# Sheet2.net
KiCad netlist of a schematic drawn in Altium Designer
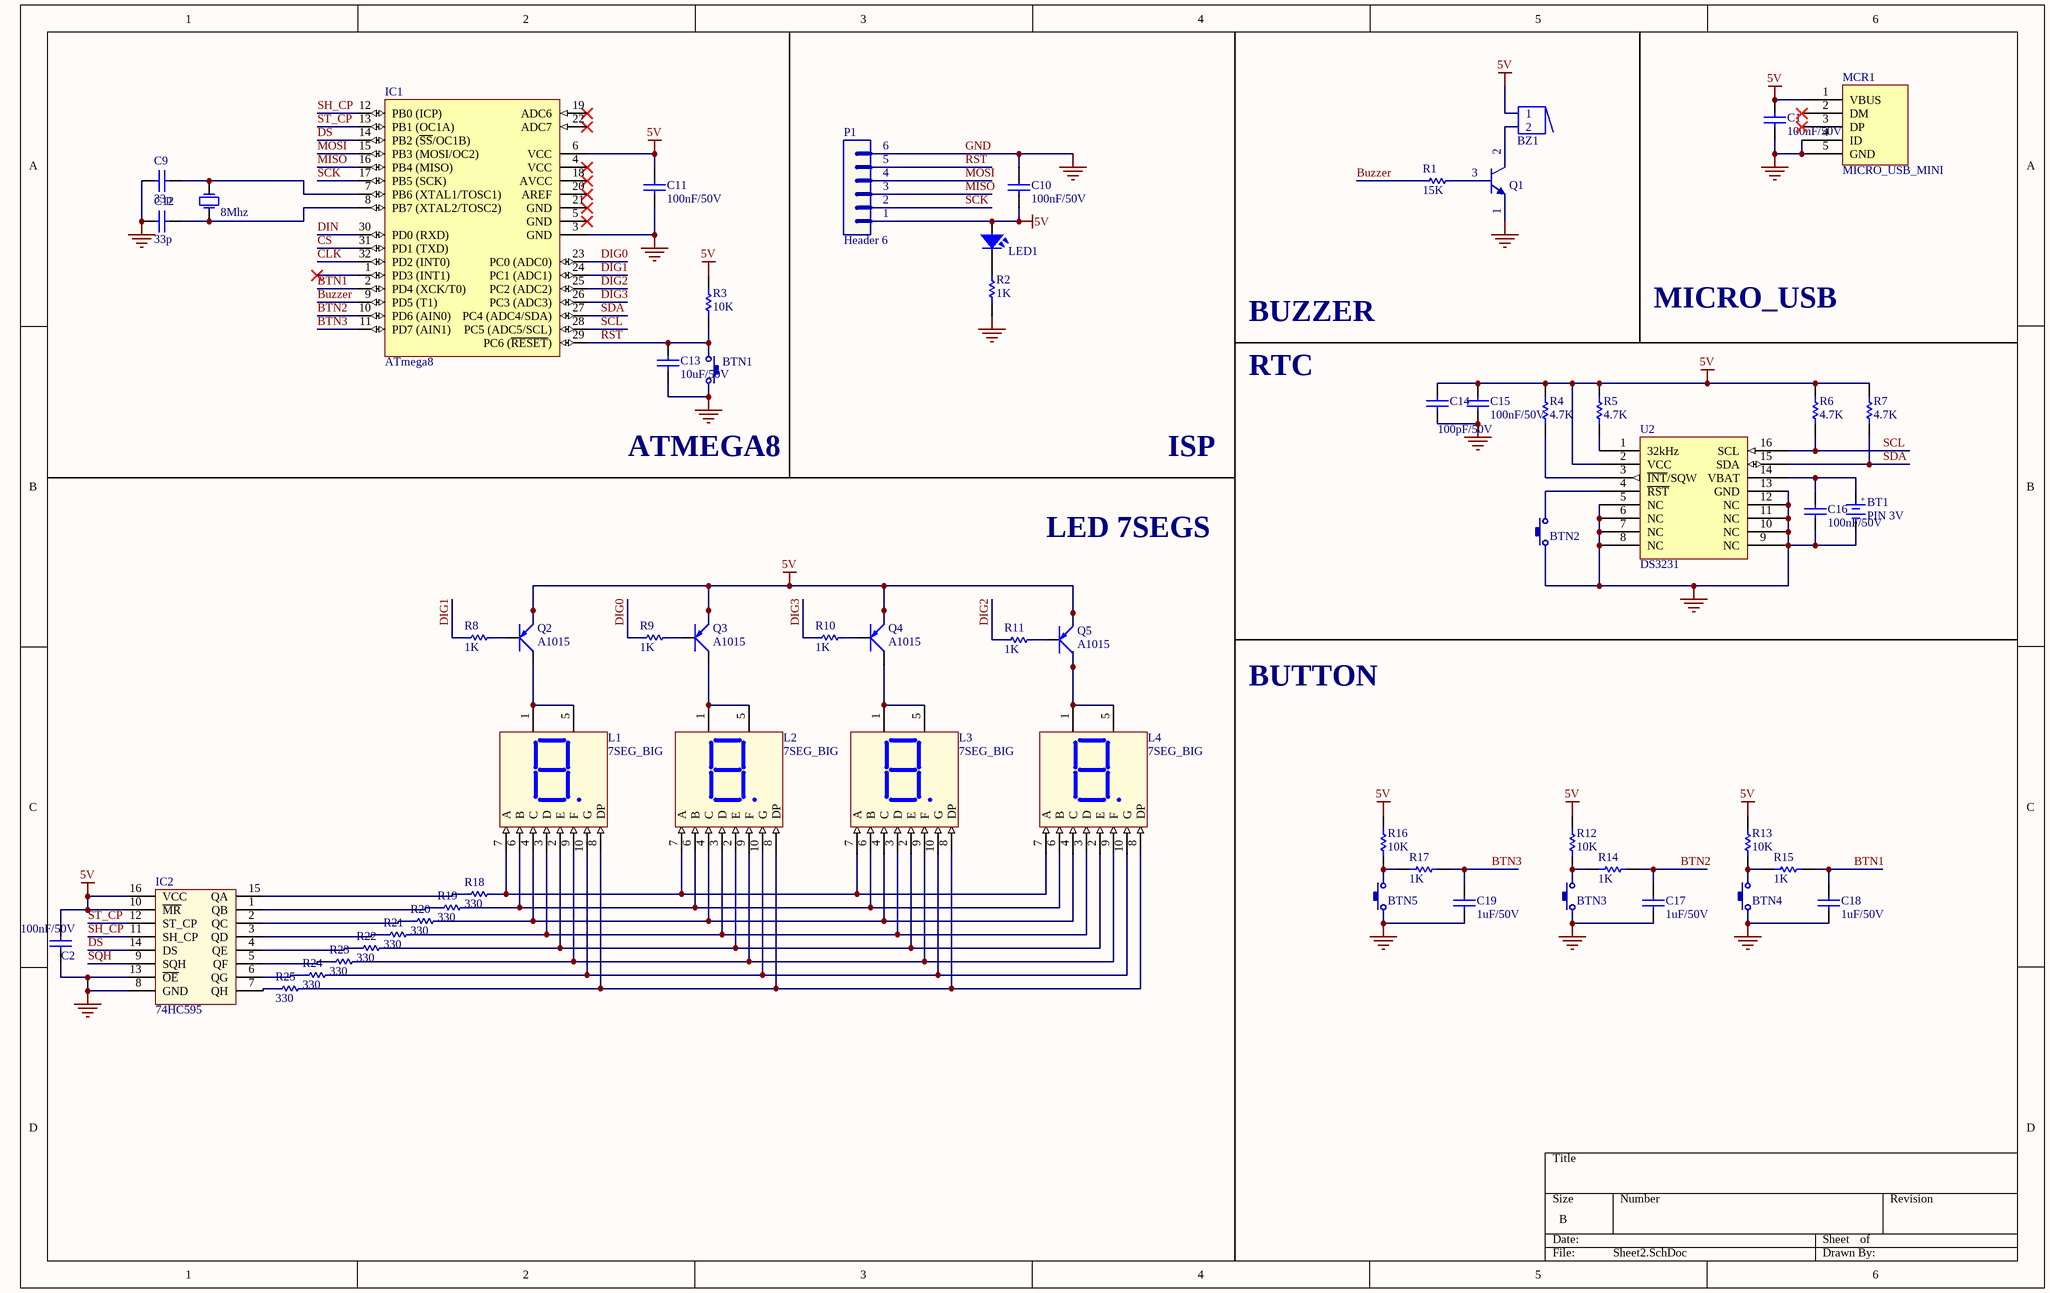
[diagram p0: Sheet2.SchDoc]

(export (version "E")
  (design (tool "Eeschema 10.0.6"))
  (components
    (comp (ref "BT1")
      (value "PIN 3V")
      (footprint "PIN3V")
      (description "Battery 3VDC")
      (libsource (lib "syhaunguyen") (part "PIN 3V"))
    )
    (comp (ref "BTN1") (value "Button") (footprint "Button") (libsource (lib "") (part "Button_1")))
    (comp (ref "BTN2")
      (value "Button")
      (footprint "Button")
      (libsource (lib "PIF_C16_2_lib") (part "Button"))
    )
    (comp (ref "BTN3")
      (value "Button")
      (footprint "Button")
      (libsource (lib "PIF_C16_2_lib") (part "Button"))
    )
    (comp (ref "BTN4")
      (value "Button")
      (footprint "Button")
      (libsource (lib "PIF_C16_2_lib") (part "Button"))
    )
    (comp (ref "BTN5")
      (value "Button")
      (footprint "Button")
      (libsource (lib "PIF_C16_2_lib") (part "Button"))
    )
    (comp (ref "BZ1") (value "Buzzer") (footprint "BUZZER") (libsource (lib "PIF_C16_2_lib") (part "Buzzer")))
    (comp (ref "C1")
      (value "100nF/50V")
      (footprint "CAP-SM-0805")
      (description "CAP CER 0.1UF 50V Y5V 0805")
      (fields
        (field (name "MANUFACTURER") "Samsung Electro-Mechanics")
        (field (name "MANUFACTURER PART NUMBER") "CL21F104ZBCNNNC")
      )
      (libsource (lib "Capacitor") (part "Cap-100nF-50V-0805"))
    )
    (comp (ref "C2")
      (value "100nF/50V")
      (footprint "CAP-SM-0805")
      (description "CAP CER 0.1UF 50V Y5V 0805")
      (fields
        (field (name "MANUFACTURER") "Samsung Electro-Mechanics")
        (field (name "MANUFACTURER PART NUMBER") "CL21F104ZBCNNNC")
      )
      (libsource (lib "Capacitor") (part "Cap-100nF-50V-0805"))
    )
    (comp (ref "C9")
      (value "33p")
      (footprint "Tu-pico")
      (description "Capacitor")
      (fields (field (name "Comment") "Capacitor Ceramic") (field (name "PUBLISHER") "Altium Limited"))
      (libsource (lib "My Library") (part "CapCeramic"))
    )
    (comp (ref "C10")
      (value "100nF/50V")
      (footprint "CAP-SM-0805")
      (description "CAP CER 0.1UF 50V Y5V 0805")
      (fields
        (field (name "MANUFACTURER") "Samsung Electro-Mechanics")
        (field (name "MANUFACTURER PART NUMBER") "CL21F104ZBCNNNC")
      )
      (libsource (lib "Capacitor") (part "Cap-100nF-50V-0805"))
    )
    (comp (ref "C11")
      (value "100nF/50V")
      (footprint "CAP-SM-0805")
      (description "CAP CER 0.1UF 50V Y5V 0805")
      (fields
        (field (name "MANUFACTURER") "Samsung Electro-Mechanics")
        (field (name "MANUFACTURER PART NUMBER") "CL21F104ZBCNNNC")
      )
      (libsource (lib "Capacitor") (part "Cap-100nF-50V-0805"))
    )
    (comp (ref "C12")
      (value "33p")
      (footprint "Tu-pico")
      (description "Capacitor")
      (fields (field (name "Comment") "Capacitor Ceramic") (field (name "PUBLISHER") "Altium Limited"))
      (libsource (lib "My Library") (part "CapCeramic"))
    )
    (comp (ref "C13")
      (value "10uF/50V")
      (footprint "CAP-SM-0805")
      (description "CAP CER 10UF 50V X5R 0805")
      (fields
        (field (name "MANUFACTURER") "Yageo")
        (field (name "MANUFACTURER PART NUMBER") "CC0805KKX5R9BB106")
      )
      (libsource (lib "Capacitor") (part "Cap-10uF-50V-0805"))
    )
    (comp (ref "C14")
      (value "100pF/50V")
      (footprint "CAP-SM-0805")
      (description "CAP CER 100PF 50V C0G/NP0 0805")
      (fields
        (field (name "MANUFACTURER") "KEMET")
        (field (name "MANUFACTURER PART NUMBER") "C0805C101J5GACTU")
      )
      (libsource (lib "Capacitor") (part "Cap-100pF-50V-0805"))
    )
    (comp (ref "C15")
      (value "100nF/50V")
      (footprint "CAP-SM-0805")
      (description "CAP CER 10UF 50V X5R 0805")
      (fields
        (field (name "MANUFACTURER") "Yageo")
        (field (name "MANUFACTURER PART NUMBER") "CC0805KKX5R9BB106")
      )
      (libsource (lib "Capacitor") (part "Cap-10uF-50V-0805"))
    )
    (comp (ref "C16")
      (value "100nF/50V")
      (footprint "CAP-SM-0805")
      (description "CAP CER 10UF 50V X5R 0805")
      (fields
        (field (name "MANUFACTURER") "Yageo")
        (field (name "MANUFACTURER PART NUMBER") "CC0805KKX5R9BB106")
      )
      (libsource (lib "Capacitor") (part "Cap-10uF-50V-0805"))
    )
    (comp (ref "C17")
      (value "1uF/50V")
      (footprint "CAP-SM-0805")
      (description "CAP CER 10UF 50V X5R 0805")
      (fields
        (field (name "MANUFACTURER") "Yageo")
        (field (name "MANUFACTURER PART NUMBER") "CC0805KKX5R9BB106")
      )
      (libsource (lib "Capacitor") (part "Cap-10uF-50V-0805"))
    )
    (comp (ref "C18")
      (value "1uF/50V")
      (footprint "CAP-SM-0805")
      (description "CAP CER 10UF 50V X5R 0805")
      (fields
        (field (name "MANUFACTURER") "Yageo")
        (field (name "MANUFACTURER PART NUMBER") "CC0805KKX5R9BB106")
      )
      (libsource (lib "Capacitor") (part "Cap-10uF-50V-0805"))
    )
    (comp (ref "C19")
      (value "1uF/50V")
      (footprint "CAP-SM-0805")
      (description "CAP CER 10UF 50V X5R 0805")
      (fields
        (field (name "MANUFACTURER") "Yageo")
        (field (name "MANUFACTURER PART NUMBER") "CC0805KKX5R9BB106")
      )
      (libsource (lib "Capacitor") (part "Cap-10uF-50V-0805"))
    )
    (comp (ref "IC1")
      (value "ATmega8")
      (footprint "32A_ATM")
      (description "8-Bit AVR Microcontroller with 8K Bytes of In-System Programmable Flash Memory")
      (libsource (lib "My Library") (part "ATmega8A-AU"))
    )
    (comp (ref "IC2")
      (value "74HC595")
      (footprint "DIP16/W0.3")
      (description "8 Bit Serial input - Parallel Output")
      (libsource (lib "My Library") (part "74595"))
    )
    (comp (ref "L1")
      (value "7SEG_BIG")
      (footprint "7SEGS_BIG 48 x 70")
      (libsource (lib "My Library") (part "7SEG_BIG"))
    )
    (comp (ref "L2")
      (value "7SEG_BIG")
      (footprint "7SEGS_BIG 48 x 70")
      (libsource (lib "My Library") (part "7SEG_BIG"))
    )
    (comp (ref "L3")
      (value "7SEG_BIG")
      (footprint "7SEGS_BIG 48 x 70")
      (libsource (lib "My Library") (part "7SEG_BIG"))
    )
    (comp (ref "L4")
      (value "7SEG_BIG")
      (footprint "7SEGS_BIG 48 x 70")
      (libsource (lib "My Library") (part "7SEG_BIG"))
    )
    (comp (ref "LED1") (value "LED") (footprint "LED 3512") (libsource (lib "My Library") (part "LED SMD")))
    (comp (ref "MCR1")
      (value "MICRO_USB_MINI")
      (footprint "USB-B-Mini")
      (libsource (lib "THU VIEN SCH") (part "MICRO_USB_MINI"))
    )
    (comp (ref "P1")
      (value "Header 6")
      (footprint "JP6")
      (description "Header, 6-Pin")
      (fields (field (name "PUBLISHER") "Altium Limited"))
      (libsource (lib "PIF_C16_2_lib") (part "Header 6"))
    )
    (comp (ref "Q1")
      (value "Transistor C1815")
      (footprint "SOT23-3 Leads")
      (libsource (lib "PIF_C16_2_lib") (part "C1815"))
    )
    (comp (ref "Q2")
      (value "A1015")
      (footprint "SOT23B")
      (description "PNP 600mW, ECB")
      (libsource (lib "syhaunguyen") (part "A1015"))
    )
    (comp (ref "Q3")
      (value "A1015")
      (footprint "SOT23B")
      (description "PNP 600mW, ECB")
      (libsource (lib "syhaunguyen") (part "A1015"))
    )
    (comp (ref "Q4")
      (value "A1015")
      (footprint "SOT23B")
      (description "PNP 600mW, ECB")
      (libsource (lib "syhaunguyen") (part "A1015"))
    )
    (comp (ref "Q5")
      (value "A1015")
      (footprint "SOT23B")
      (description "PNP 600mW, ECB")
      (libsource (lib "syhaunguyen") (part "A1015"))
    )
    (comp (ref "R1")
      (value "15K")
      (footprint "RES-SM-0805")
      (fields (field (name "Comment") "Resistor 1/4W"))
      (libsource (lib "PIF_C16_2_lib") (part "RES"))
    )
    (comp (ref "R2")
      (value "1K")
      (footprint "Resistor:RES-SM-0805")
      (description "RES 1K OHM 1% 1/4W 0805")
      (fields
        (field (name "MANUFACTURER") "Stackpole Electronics Inc")
        (field (name "MANUFACTURER PART NUMBER") "RNCP0805FTD1K00")
      )
      (libsource (lib "Resistor") (part "Res-1K-0805"))
    )
    (comp (ref "R3")
      (value "10K")
      (footprint "Resistor:RES-SM-0805")
      (description "RES 10K OHM 1% 1/4W 0805")
      (fields
        (field (name "MANUFACTURER") "Stackpole Electronics Inc")
        (field (name "MANUFACTURER PART NUMBER") "RNCP0805FTD10K0")
      )
      (libsource (lib "Resistor") (part "Res-10k-0805"))
    )
    (comp (ref "R4")
      (value "4.7K")
      (footprint "Resistor:RES-SM-0805")
      (description "RES 10K OHM 1% 1/4W 0805")
      (fields
        (field (name "MANUFACTURER") "Stackpole Electronics Inc")
        (field (name "MANUFACTURER PART NUMBER") "RNCP0805FTD10K0")
      )
      (libsource (lib "Resistor") (part "Res-10k-0805"))
    )
    (comp (ref "R5")
      (value "4.7K")
      (footprint "Resistor:RES-SM-0805")
      (description "RES 10K OHM 1% 1/4W 0805")
      (fields
        (field (name "MANUFACTURER") "Stackpole Electronics Inc")
        (field (name "MANUFACTURER PART NUMBER") "RNCP0805FTD10K0")
      )
      (libsource (lib "Resistor") (part "Res-10k-0805"))
    )
    (comp (ref "R6")
      (value "4.7K")
      (footprint "Resistor:RES-SM-0805")
      (description "RES 10K OHM 1% 1/4W 0805")
      (fields
        (field (name "MANUFACTURER") "Stackpole Electronics Inc")
        (field (name "MANUFACTURER PART NUMBER") "RNCP0805FTD10K0")
      )
      (libsource (lib "Resistor") (part "Res-10k-0805"))
    )
    (comp (ref "R7")
      (value "4.7K")
      (footprint "Resistor:RES-SM-0805")
      (description "RES 10K OHM 1% 1/4W 0805")
      (fields
        (field (name "MANUFACTURER") "Stackpole Electronics Inc")
        (field (name "MANUFACTURER PART NUMBER") "RNCP0805FTD10K0")
      )
      (libsource (lib "Resistor") (part "Res-10k-0805"))
    )
    (comp (ref "R8")
      (value "1K")
      (footprint "RES-SM-0805")
      (fields (field (name "Comment") "Resistor 1/4W"))
      (libsource (lib "PIF_C16_2_lib") (part "RES"))
    )
    (comp (ref "R9")
      (value "1K")
      (footprint "RES-SM-0805")
      (fields (field (name "Comment") "Resistor 1/4W"))
      (libsource (lib "PIF_C16_2_lib") (part "RES"))
    )
    (comp (ref "R10")
      (value "1K")
      (footprint "RES-SM-0805")
      (fields (field (name "Comment") "Resistor 1/4W"))
      (libsource (lib "PIF_C16_2_lib") (part "RES"))
    )
    (comp (ref "R11")
      (value "1K")
      (footprint "RES-SM-0805")
      (fields (field (name "Comment") "Resistor 1/4W"))
      (libsource (lib "PIF_C16_2_lib") (part "RES"))
    )
    (comp (ref "R12")
      (value "10K")
      (footprint "Resistor:RES-SM-0805")
      (description "RES 1K OHM 1% 1/4W 0805")
      (fields
        (field (name "MANUFACTURER") "Stackpole Electronics Inc")
        (field (name "MANUFACTURER PART NUMBER") "RNCP0805FTD1K00")
      )
      (libsource (lib "Resistor") (part "Res-1K-0805"))
    )
    (comp (ref "R13")
      (value "10K")
      (footprint "Resistor:RES-SM-0805")
      (description "RES 1K OHM 1% 1/4W 0805")
      (fields
        (field (name "MANUFACTURER") "Stackpole Electronics Inc")
        (field (name "MANUFACTURER PART NUMBER") "RNCP0805FTD1K00")
      )
      (libsource (lib "Resistor") (part "Res-1K-0805"))
    )
    (comp (ref "R14")
      (value "1K")
      (footprint "Resistor:RES-SM-0805")
      (description "RES 1K OHM 1% 1/4W 0805")
      (fields
        (field (name "MANUFACTURER") "Stackpole Electronics Inc")
        (field (name "MANUFACTURER PART NUMBER") "RNCP0805FTD1K00")
      )
      (libsource (lib "Resistor") (part "Res-1K-0805"))
    )
    (comp (ref "R15")
      (value "1K")
      (footprint "Resistor:RES-SM-0805")
      (description "RES 1K OHM 1% 1/4W 0805")
      (fields
        (field (name "MANUFACTURER") "Stackpole Electronics Inc")
        (field (name "MANUFACTURER PART NUMBER") "RNCP0805FTD1K00")
      )
      (libsource (lib "Resistor") (part "Res-1K-0805"))
    )
    (comp (ref "R16")
      (value "10K")
      (footprint "Resistor:RES-SM-0805")
      (description "RES 1K OHM 1% 1/4W 0805")
      (fields
        (field (name "MANUFACTURER") "Stackpole Electronics Inc")
        (field (name "MANUFACTURER PART NUMBER") "RNCP0805FTD1K00")
      )
      (libsource (lib "Resistor") (part "Res-1K-0805"))
    )
    (comp (ref "R17")
      (value "1K")
      (footprint "Resistor:RES-SM-0805")
      (description "RES 1K OHM 1% 1/4W 0805")
      (fields
        (field (name "MANUFACTURER") "Stackpole Electronics Inc")
        (field (name "MANUFACTURER PART NUMBER") "RNCP0805FTD1K00")
      )
      (libsource (lib "Resistor") (part "Res-1K-0805"))
    )
    (comp (ref "R18")
      (value "330")
      (footprint "RES-SM-0805")
      (fields (field (name "Comment") "Resistor 1/4W"))
      (libsource (lib "PIF_C16_2_lib") (part "RES"))
    )
    (comp (ref "R19")
      (value "330")
      (footprint "RES-SM-0805")
      (fields (field (name "Comment") "Resistor 1/4W"))
      (libsource (lib "PIF_C16_2_lib") (part "RES"))
    )
    (comp (ref "R20")
      (value "330")
      (footprint "RES-SM-0805")
      (fields (field (name "Comment") "Resistor 1/4W"))
      (libsource (lib "PIF_C16_2_lib") (part "RES"))
    )
    (comp (ref "R21")
      (value "330")
      (footprint "RES-SM-0805")
      (fields (field (name "Comment") "Resistor 1/4W"))
      (libsource (lib "PIF_C16_2_lib") (part "RES"))
    )
    (comp (ref "R22")
      (value "330")
      (footprint "RES-SM-0805")
      (fields (field (name "Comment") "Resistor 1/4W"))
      (libsource (lib "PIF_C16_2_lib") (part "RES"))
    )
    (comp (ref "R23")
      (value "330")
      (footprint "RES-SM-0805")
      (fields (field (name "Comment") "Resistor 1/4W"))
      (libsource (lib "PIF_C16_2_lib") (part "RES"))
    )
    (comp (ref "R24")
      (value "330")
      (footprint "RES-SM-0805")
      (fields (field (name "Comment") "Resistor 1/4W"))
      (libsource (lib "PIF_C16_2_lib") (part "RES"))
    )
    (comp (ref "R25")
      (value "330")
      (footprint "RES-SM-0805")
      (fields (field (name "Comment") "Resistor 1/4W"))
      (libsource (lib "PIF_C16_2_lib") (part "RES"))
    )
    (comp (ref "U2") (value "DS3231") (footprint "SL3016") (libsource (lib "My Library") (part "DS3231")))
    (comp (ref "Y1")
      (value "8Mhz")
      (footprint "XTAL")
      (description "Crystal Oscillator")
      (fields (field (name "PUBLISHER") "Altium Limited"))
      (libsource (lib "My Library") (part "XTAL"))
    )
  )
  (nets
    (net (code "1") (name "/BTN1") (class "Default")
      (node (ref "C18") (pin "1") (pinfunction "1_1") (pintype "passive"))
      (node (ref "IC1") (pin "2") (pinfunction "PD4_(XCK/T0)_2") (pintype "bidirectional"))
      (node (ref "R15") (pin "2") (pinfunction "2_2") (pintype "passive"))
    )
    (net (code "2") (name "/BTN2") (class "Default")
      (node (ref "C17") (pin "1") (pinfunction "1_1") (pintype "passive"))
      (node (ref "IC1") (pin "10") (pinfunction "PD6_(AIN0)_10") (pintype "bidirectional"))
      (node (ref "R14") (pin "2") (pinfunction "2_2") (pintype "passive"))
    )
    (net (code "3") (name "/BTN3") (class "Default")
      (node (ref "C19") (pin "1") (pinfunction "1_1") (pintype "passive"))
      (node (ref "IC1") (pin "11") (pinfunction "PD7_(AIN1)_11") (pintype "bidirectional"))
      (node (ref "R17") (pin "2") (pinfunction "2_2") (pintype "passive"))
    )
    (net (code "4") (name "/Buzzer") (class "Default")
      (node (ref "IC1") (pin "9") (pinfunction "PD5_(T1)_9") (pintype "bidirectional"))
      (node (ref "R1") (pin "1") (pintype "passive"))
    )
    (net (code "5") (name "/CLK") (class "Default")
      (node (ref "IC1") (pin "32") (pinfunction "PD2_(INT0)_32") (pintype "bidirectional"))
    )
    (net (code "6") (name "/CS") (class "Default")
      (node (ref "IC1") (pin "31") (pinfunction "PD1_(TXD)_31") (pintype "bidirectional"))
    )
    (net (code "7") (name "/DIG0") (class "Default")
      (node (ref "IC1") (pin "23") (pinfunction "PC0_(ADC0)_23") (pintype "bidirectional"))
      (node (ref "R9") (pin "1") (pintype "passive"))
    )
    (net (code "8") (name "/DIG1") (class "Default")
      (node (ref "IC1") (pin "24") (pinfunction "PC1_(ADC1)_24") (pintype "bidirectional"))
      (node (ref "R8") (pin "1") (pintype "passive"))
    )
    (net (code "9") (name "/DIG2") (class "Default")
      (node (ref "IC1") (pin "25") (pinfunction "PC2_(ADC2)_25") (pintype "bidirectional"))
      (node (ref "R11") (pin "1") (pintype "passive"))
    )
    (net (code "10") (name "/DIG3") (class "Default")
      (node (ref "IC1") (pin "26") (pinfunction "PC3_(ADC3)_26") (pintype "bidirectional"))
      (node (ref "R10") (pin "1") (pintype "passive"))
    )
    (net (code "11") (name "/DIN") (class "Default")
      (node (ref "IC1") (pin "30") (pinfunction "PD0_(RXD)_30") (pintype "bidirectional"))
    )
    (net (code "12") (name "/DS") (class "Default")
      (node (ref "IC1") (pin "14") (pinfunction "PB2_(~{SS}/OC1B)_14") (pintype "bidirectional"))
      (node (ref "IC2") (pin "14") (pinfunction "DS_14") (pintype "passive"))
    )
    (net (code "13") (name "/MISO") (class "Default")
      (node (ref "IC1") (pin "16") (pinfunction "PB4_(MISO)_16") (pintype "bidirectional"))
      (node (ref "P1") (pin "3") (pinfunction "3_3") (pintype "passive"))
    )
    (net (code "14") (name "/MOSI") (class "Default")
      (node (ref "IC1") (pin "15") (pinfunction "PB3_(MOSI/OC2)_15") (pintype "bidirectional"))
      (node (ref "P1") (pin "4") (pinfunction "4_4") (pintype "passive"))
    )
    (net (code "15") (name "/RST") (class "Default")
      (node (ref "BTN1") (pin "1") (pintype "passive"))
      (node (ref "C13") (pin "2") (pinfunction "2_2") (pintype "passive"))
      (node (ref "IC1") (pin "29") (pinfunction "PC6_(~{RESET})_29") (pintype "bidirectional"))
      (node (ref "P1") (pin "5") (pinfunction "5_5") (pintype "passive"))
      (node (ref "R3") (pin "1") (pinfunction "1_1") (pintype "passive"))
    )
    (net (code "16") (name "/SCK") (class "Default")
      (node (ref "IC1") (pin "17") (pinfunction "PB5_(SCK)_17") (pintype "bidirectional"))
      (node (ref "P1") (pin "2") (pinfunction "2_2") (pintype "passive"))
    )
    (net (code "17") (name "/SCL") (class "Default")
      (node (ref "IC1") (pin "28") (pinfunction "PC5_(ADC5/SCL)_28") (pintype "bidirectional"))
      (node (ref "R6") (pin "1") (pinfunction "1_1") (pintype "passive"))
      (node (ref "U2") (pin "16") (pinfunction "SCL_16") (pintype "input"))
    )
    (net (code "18") (name "/SDA") (class "Default")
      (node (ref "IC1") (pin "27") (pinfunction "PC4_(ADC4/SDA)_27") (pintype "bidirectional"))
      (node (ref "R7") (pin "1") (pinfunction "1_1") (pintype "passive"))
      (node (ref "U2") (pin "15") (pinfunction "SDA_15") (pintype "bidirectional"))
    )
    (net (code "19") (name "/SH_CP") (class "Default")
      (node (ref "IC1") (pin "12") (pinfunction "PB0_(ICP)_12") (pintype "bidirectional"))
      (node (ref "IC2") (pin "11") (pinfunction "SH_CP_11") (pintype "passive"))
    )
    (net (code "20") (name "/SQH") (class "Default")
      (node (ref "IC2") (pin "9") (pinfunction "SQH_9") (pintype "passive"))
    )
    (net (code "21") (name "/ST_CP") (class "Default")
      (node (ref "IC1") (pin "13") (pinfunction "PB1_(OC1A)_13") (pintype "bidirectional"))
      (node (ref "IC2") (pin "12") (pinfunction "ST_CP_12") (pintype "passive"))
    )
    (net (code "22") (name "5V") (class "Default")
      (node (ref "BZ1") (pin "1") (pinfunction "1_1") (pintype "passive"))
      (node (ref "C1") (pin "2") (pinfunction "2_2") (pintype "passive"))
      (node (ref "C10") (pin "1") (pinfunction "1_1") (pintype "passive"))
      (node (ref "C11") (pin "2") (pinfunction "2_2") (pintype "passive"))
      (node (ref "C14") (pin "2") (pinfunction "2_2") (pintype "passive"))
      (node (ref "C15") (pin "2") (pinfunction "2_2") (pintype "passive"))
      (node (ref "C2") (pin "2") (pinfunction "2_2") (pintype "passive"))
      (node (ref "IC1") (pin "6") (pinfunction "VCC_6") (pintype "power_in"))
      (node (ref "IC2") (pin "10") (pinfunction "~{MR}_10") (pintype "passive"))
      (node (ref "IC2") (pin "16") (pinfunction "VCC_16") (pintype "passive"))
      (node (ref "LED1") (pin "1") (pinfunction "1_1") (pintype "passive"))
      (node (ref "MCR1") (pin "1") (pinfunction "VBUS_1") (pintype "passive"))
      (node (ref "P1") (pin "1") (pinfunction "1_1") (pintype "passive"))
      (node (ref "Q2") (pin "1") (pinfunction "E_1") (pintype "passive"))
      (node (ref "Q3") (pin "1") (pinfunction "E_1") (pintype "passive"))
      (node (ref "Q4") (pin "1") (pinfunction "E_1") (pintype "passive"))
      (node (ref "Q5") (pin "1") (pinfunction "E_1") (pintype "passive"))
      (node (ref "R12") (pin "2") (pinfunction "2_2") (pintype "passive"))
      (node (ref "R13") (pin "2") (pinfunction "2_2") (pintype "passive"))
      (node (ref "R16") (pin "2") (pinfunction "2_2") (pintype "passive"))
      (node (ref "R3") (pin "2") (pinfunction "2_2") (pintype "passive"))
      (node (ref "R4") (pin "2") (pinfunction "2_2") (pintype "passive"))
      (node (ref "R5") (pin "2") (pinfunction "2_2") (pintype "passive"))
      (node (ref "R6") (pin "2") (pinfunction "2_2") (pintype "passive"))
      (node (ref "R7") (pin "2") (pinfunction "2_2") (pintype "passive"))
      (node (ref "U2") (pin "2") (pinfunction "VCC_2") (pintype "passive"))
    )
    (net (code "23") (name "GND") (class "Default")
      (node (ref "BT1") (pin "2") (pinfunction "GND_2") (pintype "passive"))
      (node (ref "BTN1") (pin "2") (pintype "passive"))
      (node (ref "BTN2") (pin "1") (pintype "passive"))
      (node (ref "BTN3") (pin "1") (pintype "passive"))
      (node (ref "BTN4") (pin "1") (pintype "passive"))
      (node (ref "BTN5") (pin "1") (pintype "passive"))
      (node (ref "C1") (pin "1") (pinfunction "1_1") (pintype "passive"))
      (node (ref "C10") (pin "2") (pinfunction "2_2") (pintype "passive"))
      (node (ref "C11") (pin "1") (pinfunction "1_1") (pintype "passive"))
      (node (ref "C12") (pin "1") (pinfunction "1_1") (pintype "passive"))
      (node (ref "C13") (pin "1") (pinfunction "1_1") (pintype "passive"))
      (node (ref "C14") (pin "1") (pinfunction "1_1") (pintype "passive"))
      (node (ref "C15") (pin "1") (pinfunction "1_1") (pintype "passive"))
      (node (ref "C16") (pin "1") (pinfunction "1_1") (pintype "passive"))
      (node (ref "C17") (pin "2") (pinfunction "2_2") (pintype "passive"))
      (node (ref "C18") (pin "2") (pinfunction "2_2") (pintype "passive"))
      (node (ref "C19") (pin "2") (pinfunction "2_2") (pintype "passive"))
      (node (ref "C2") (pin "1") (pinfunction "1_1") (pintype "passive"))
      (node (ref "C9") (pin "1") (pinfunction "1_1") (pintype "passive"))
      (node (ref "IC1") (pin "3") (pinfunction "GND_3") (pintype "power_in"))
      (node (ref "IC2") (pin "13") (pinfunction "~{OE}_13") (pintype "passive"))
      (node (ref "IC2") (pin "8") (pinfunction "GND_8") (pintype "passive"))
      (node (ref "MCR1") (pin "4") (pinfunction "ID_4") (pintype "passive"))
      (node (ref "MCR1") (pin "5") (pinfunction "GND_5") (pintype "passive"))
      (node (ref "P1") (pin "6") (pinfunction "6_6") (pintype "passive"))
      (node (ref "Q1") (pin "1") (pinfunction "E_1") (pintype "passive"))
      (node (ref "R2") (pin "1") (pinfunction "1_1") (pintype "passive"))
      (node (ref "U2") (pin "10") (pinfunction "NC_10") (pintype "passive"))
      (node (ref "U2") (pin "11") (pinfunction "NC_11") (pintype "passive"))
      (node (ref "U2") (pin "12") (pinfunction "NC_12") (pintype "passive"))
      (node (ref "U2") (pin "13") (pinfunction "GND_13") (pintype "passive"))
      (node (ref "U2") (pin "5") (pinfunction "NC_5") (pintype "passive"))
      (node (ref "U2") (pin "6") (pinfunction "NC_6") (pintype "passive"))
      (node (ref "U2") (pin "7") (pinfunction "NC_7") (pintype "passive"))
      (node (ref "U2") (pin "8") (pinfunction "NC_8") (pintype "passive"))
      (node (ref "U2") (pin "9") (pinfunction "NC_9") (pintype "passive"))
    )
    (net (code "24") (name "Net-(BT1-+3V)") (class "Default")
      (node (ref "BT1") (pin "1") (pinfunction "+3V_1") (pintype "passive"))
      (node (ref "C16") (pin "2") (pinfunction "2_2") (pintype "passive"))
      (node (ref "U2") (pin "14") (pinfunction "VBAT_14") (pintype "passive"))
    )
    (net (code "25") (name "Net-(BTN3-Pad2)") (class "Default")
      (node (ref "BTN3") (pin "2") (pintype "passive"))
      (node (ref "R12") (pin "1") (pinfunction "1_1") (pintype "passive"))
      (node (ref "R14") (pin "1") (pinfunction "1_1") (pintype "passive"))
    )
    (net (code "26") (name "Net-(BTN4-Pad2)") (class "Default")
      (node (ref "BTN4") (pin "2") (pintype "passive"))
      (node (ref "R13") (pin "1") (pinfunction "1_1") (pintype "passive"))
      (node (ref "R15") (pin "1") (pinfunction "1_1") (pintype "passive"))
    )
    (net (code "27") (name "Net-(BTN5-Pad2)") (class "Default")
      (node (ref "BTN5") (pin "2") (pintype "passive"))
      (node (ref "R16") (pin "1") (pinfunction "1_1") (pintype "passive"))
      (node (ref "R17") (pin "1") (pinfunction "1_1") (pintype "passive"))
    )
    (net (code "28") (name "Net-(IC1-PB6_(XTAL1{slash}TOSC1))") (class "Default")
      (node (ref "C9") (pin "2") (pinfunction "2_2") (pintype "passive"))
      (node (ref "IC1") (pin "7") (pinfunction "PB6_(XTAL1/TOSC1)_7") (pintype "bidirectional"))
      (node (ref "Y1") (pin "2") (pinfunction "OSC2_2") (pintype "passive"))
    )
    (net (code "29") (name "Net-(IC1-PB7_(XTAL2{slash}TOSC2))") (class "Default")
      (node (ref "C12") (pin "2") (pinfunction "2_2") (pintype "passive"))
      (node (ref "IC1") (pin "8") (pinfunction "PB7_(XTAL2/TOSC2)_8") (pintype "bidirectional"))
      (node (ref "Y1") (pin "1") (pinfunction "OSC1_1") (pintype "passive"))
    )
    (net (code "30") (name "Net-(IC2-QA)") (class "Default")
      (node (ref "IC2") (pin "15") (pinfunction "QA_15") (pintype "passive"))
      (node (ref "R18") (pin "1") (pintype "passive"))
    )
    (net (code "31") (name "Net-(IC2-QB)") (class "Default")
      (node (ref "IC2") (pin "1") (pinfunction "QB_1") (pintype "passive"))
      (node (ref "R19") (pin "1") (pintype "passive"))
    )
    (net (code "32") (name "Net-(IC2-QC)") (class "Default")
      (node (ref "IC2") (pin "2") (pinfunction "QC_2") (pintype "passive"))
      (node (ref "R20") (pin "1") (pintype "passive"))
    )
    (net (code "33") (name "Net-(IC2-QD)") (class "Default")
      (node (ref "IC2") (pin "3") (pinfunction "QD_3") (pintype "passive"))
      (node (ref "R21") (pin "1") (pintype "passive"))
    )
    (net (code "34") (name "Net-(IC2-QE)") (class "Default")
      (node (ref "IC2") (pin "4") (pinfunction "QE_4") (pintype "passive"))
      (node (ref "R22") (pin "1") (pintype "passive"))
    )
    (net (code "35") (name "Net-(IC2-QF)") (class "Default")
      (node (ref "IC2") (pin "5") (pinfunction "QF_5") (pintype "passive"))
      (node (ref "R23") (pin "1") (pintype "passive"))
    )
    (net (code "36") (name "Net-(IC2-QG)") (class "Default")
      (node (ref "IC2") (pin "6") (pinfunction "QG_6") (pintype "passive"))
      (node (ref "R24") (pin "1") (pintype "passive"))
    )
    (net (code "37") (name "Net-(IC2-QH)") (class "Default")
      (node (ref "IC2") (pin "7") (pinfunction "QH_7") (pintype "passive"))
      (node (ref "R25") (pin "1") (pintype "passive"))
    )
    (net (code "38") (name "Net-(L1-A)") (class "Default")
      (node (ref "L1") (pin "7") (pinfunction "A_7") (pintype "input"))
      (node (ref "L2") (pin "7") (pinfunction "A_7") (pintype "input"))
      (node (ref "L3") (pin "7") (pinfunction "A_7") (pintype "input"))
      (node (ref "L4") (pin "7") (pinfunction "A_7") (pintype "input"))
      (node (ref "R18") (pin "2") (pintype "passive"))
    )
    (net (code "39") (name "Net-(L1-B)") (class "Default")
      (node (ref "L1") (pin "6") (pinfunction "B_6") (pintype "input"))
      (node (ref "L2") (pin "6") (pinfunction "B_6") (pintype "input"))
      (node (ref "L3") (pin "6") (pinfunction "B_6") (pintype "input"))
      (node (ref "L4") (pin "6") (pinfunction "B_6") (pintype "input"))
      (node (ref "R19") (pin "2") (pintype "passive"))
    )
    (net (code "40") (name "Net-(L1-C)") (class "Default")
      (node (ref "L1") (pin "4") (pinfunction "C_4") (pintype "input"))
      (node (ref "L2") (pin "4") (pinfunction "C_4") (pintype "input"))
      (node (ref "L3") (pin "4") (pinfunction "C_4") (pintype "input"))
      (node (ref "L4") (pin "4") (pinfunction "C_4") (pintype "input"))
      (node (ref "R20") (pin "2") (pintype "passive"))
    )
    (net (code "41") (name "Net-(L1-D)") (class "Default")
      (node (ref "L1") (pin "3") (pinfunction "D_3") (pintype "input"))
      (node (ref "L2") (pin "3") (pinfunction "D_3") (pintype "input"))
      (node (ref "L3") (pin "3") (pinfunction "D_3") (pintype "input"))
      (node (ref "L4") (pin "3") (pinfunction "D_3") (pintype "input"))
      (node (ref "R21") (pin "2") (pintype "passive"))
    )
    (net (code "42") (name "Net-(L1-DP)") (class "Default")
      (node (ref "L1") (pin "8") (pinfunction "DP_8") (pintype "input"))
      (node (ref "L2") (pin "8") (pinfunction "DP_8") (pintype "input"))
      (node (ref "L3") (pin "8") (pinfunction "DP_8") (pintype "input"))
      (node (ref "L4") (pin "8") (pinfunction "DP_8") (pintype "input"))
      (node (ref "R25") (pin "2") (pintype "passive"))
    )
    (net (code "43") (name "Net-(L1-E)") (class "Default")
      (node (ref "L1") (pin "2") (pinfunction "E_2") (pintype "input"))
      (node (ref "L2") (pin "2") (pinfunction "E_2") (pintype "input"))
      (node (ref "L3") (pin "2") (pinfunction "E_2") (pintype "input"))
      (node (ref "L4") (pin "2") (pinfunction "E_2") (pintype "input"))
      (node (ref "R22") (pin "2") (pintype "passive"))
    )
    (net (code "44") (name "Net-(L1-F)") (class "Default")
      (node (ref "L1") (pin "9") (pinfunction "F_9") (pintype "input"))
      (node (ref "L2") (pin "9") (pinfunction "F_9") (pintype "input"))
      (node (ref "L3") (pin "9") (pinfunction "F_9") (pintype "input"))
      (node (ref "L4") (pin "9") (pinfunction "F_9") (pintype "input"))
      (node (ref "R23") (pin "2") (pintype "passive"))
    )
    (net (code "45") (name "Net-(L1-G)") (class "Default")
      (node (ref "L1") (pin "10") (pinfunction "G_10") (pintype "input"))
      (node (ref "L2") (pin "10") (pinfunction "G_10") (pintype "input"))
      (node (ref "L3") (pin "10") (pinfunction "G_10") (pintype "input"))
      (node (ref "L4") (pin "10") (pinfunction "G_10") (pintype "input"))
      (node (ref "R24") (pin "2") (pintype "passive"))
    )
    (net (code "46") (name "Net-(LED1-Pad2)") (class "Default")
      (node (ref "LED1") (pin "2") (pinfunction "2_2") (pintype "passive"))
      (node (ref "R2") (pin "2") (pinfunction "2_2") (pintype "passive"))
    )
    (net (code "47") (name "Net-(Q1-B)") (class "Default")
      (node (ref "Q1") (pin "3") (pinfunction "B_3") (pintype "passive"))
      (node (ref "R1") (pin "2") (pintype "passive"))
    )
    (net (code "48") (name "Net-(Q1-C)") (class "Default")
      (node (ref "BZ1") (pin "2") (pinfunction "2_2") (pintype "passive"))
      (node (ref "Q1") (pin "2") (pinfunction "C_2") (pintype "passive"))
    )
    (net (code "49") (name "Net-(Q2-B)") (class "Default")
      (node (ref "Q2") (pin "3") (pinfunction "B_3") (pintype "passive"))
      (node (ref "R8") (pin "2") (pintype "passive"))
    )
    (net (code "50") (name "Net-(Q2-C)") (class "Default")
      (node (ref "L1") (pin "1") (pinfunction "AC_1") (pintype "power_in"))
      (node (ref "L1") (pin "5") (pinfunction "AC_5") (pintype "power_in"))
      (node (ref "Q2") (pin "2") (pinfunction "C_2") (pintype "passive"))
    )
    (net (code "51") (name "Net-(Q3-B)") (class "Default")
      (node (ref "Q3") (pin "3") (pinfunction "B_3") (pintype "passive"))
      (node (ref "R9") (pin "2") (pintype "passive"))
    )
    (net (code "52") (name "Net-(Q3-C)") (class "Default")
      (node (ref "L2") (pin "1") (pinfunction "AC_1") (pintype "power_in"))
      (node (ref "L2") (pin "5") (pinfunction "AC_5") (pintype "power_in"))
      (node (ref "Q3") (pin "2") (pinfunction "C_2") (pintype "passive"))
    )
    (net (code "53") (name "Net-(Q4-B)") (class "Default")
      (node (ref "Q4") (pin "3") (pinfunction "B_3") (pintype "passive"))
      (node (ref "R10") (pin "2") (pintype "passive"))
    )
    (net (code "54") (name "Net-(Q4-C)") (class "Default")
      (node (ref "L3") (pin "1") (pinfunction "AC_1") (pintype "power_in"))
      (node (ref "L3") (pin "5") (pinfunction "AC_5") (pintype "power_in"))
      (node (ref "Q4") (pin "2") (pinfunction "C_2") (pintype "passive"))
    )
    (net (code "55") (name "Net-(Q5-B)") (class "Default")
      (node (ref "Q5") (pin "3") (pinfunction "B_3") (pintype "passive"))
      (node (ref "R11") (pin "2") (pintype "passive"))
    )
    (net (code "56") (name "Net-(Q5-C)") (class "Default")
      (node (ref "L4") (pin "1") (pinfunction "AC_1") (pintype "power_in"))
      (node (ref "L4") (pin "5") (pinfunction "AC_5") (pintype "power_in"))
      (node (ref "Q5") (pin "2") (pinfunction "C_2") (pintype "passive"))
    )
    (net (code "57") (name "Net-(U2-32kHz)") (class "Default")
      (node (ref "R5") (pin "1") (pinfunction "1_1") (pintype "passive"))
      (node (ref "U2") (pin "1") (pinfunction "32kHz_1") (pintype "passive"))
    )
    (net (code "58") (name "Net-(U2-~{INT}{slash}SQW)") (class "Default")
      (node (ref "R4") (pin "1") (pinfunction "1_1") (pintype "passive"))
      (node (ref "U2") (pin "3") (pinfunction "~{INT}/SQW_3") (pintype "output"))
    )
    (net (code "59") (name "Net-(U2-~{RST})") (class "Default")
      (node (ref "BTN2") (pin "2") (pintype "passive"))
      (node (ref "U2") (pin "4") (pinfunction "~{RST}_4") (pintype "passive"))
    )
    (net (code "60") (name "VCC") (class "Default")
      (node (ref "IC2") (pin "16") (pinfunction "VCC_16") (pintype "passive"))
    )
    (net (code "61") (name "unconnected-(IC1-ADC6-Pad19)") (class "Default")
      (node (ref "IC1") (pin "19") (pinfunction "ADC6_19") (pintype "input+no_connect"))
    )
    (net (code "62") (name "unconnected-(IC1-ADC7-Pad22)") (class "Default")
      (node (ref "IC1") (pin "22") (pinfunction "ADC7_22") (pintype "input+no_connect"))
    )
    (net (code "63") (name "unconnected-(IC1-AREF-Pad20)") (class "Default")
      (node (ref "IC1") (pin "20") (pinfunction "AREF_20") (pintype "passive+no_connect"))
    )
    (net (code "64") (name "unconnected-(IC1-AVCC-Pad18)") (class "Default")
      (node (ref "IC1") (pin "18") (pinfunction "AVCC_18") (pintype "power_in+no_connect"))
    )
    (net (code "65") (name "unconnected-(IC1-GND-Pad5)") (class "Default")
      (node (ref "IC1") (pin "5") (pinfunction "GND_5") (pintype "power_in+no_connect"))
    )
    (net (code "66") (name "unconnected-(IC1-GND-Pad21)") (class "Default")
      (node (ref "IC1") (pin "21") (pinfunction "GND_21") (pintype "power_in+no_connect"))
    )
    (net (code "67") (name "unconnected-(IC1-PD3_(INT1)-Pad1)") (class "Default")
      (node (ref "IC1") (pin "1") (pinfunction "PD3_(INT1)_1") (pintype "bidirectional+no_connect"))
    )
    (net (code "68") (name "unconnected-(IC1-VCC-Pad4)") (class "Default")
      (node (ref "IC1") (pin "4") (pinfunction "VCC_4") (pintype "power_in+no_connect"))
    )
    (net (code "69") (name "unconnected-(IC2-GND-Pad8)") (class "Default")
      (node (ref "IC2") (pin "8") (pinfunction "GND_8") (pintype "passive"))
    )
    (net (code "70") (name "unconnected-(MCR1-DM-Pad2)") (class "Default")
      (node (ref "MCR1") (pin "2") (pinfunction "DM_2") (pintype "passive+no_connect"))
    )
    (net (code "71") (name "unconnected-(MCR1-DP-Pad3)") (class "Default")
      (node (ref "MCR1") (pin "3") (pinfunction "DP_3") (pintype "passive+no_connect"))
    )
  )
)
